# captivate_bswp.net
KiCad netlist of a schematic drawn in Altium Designer
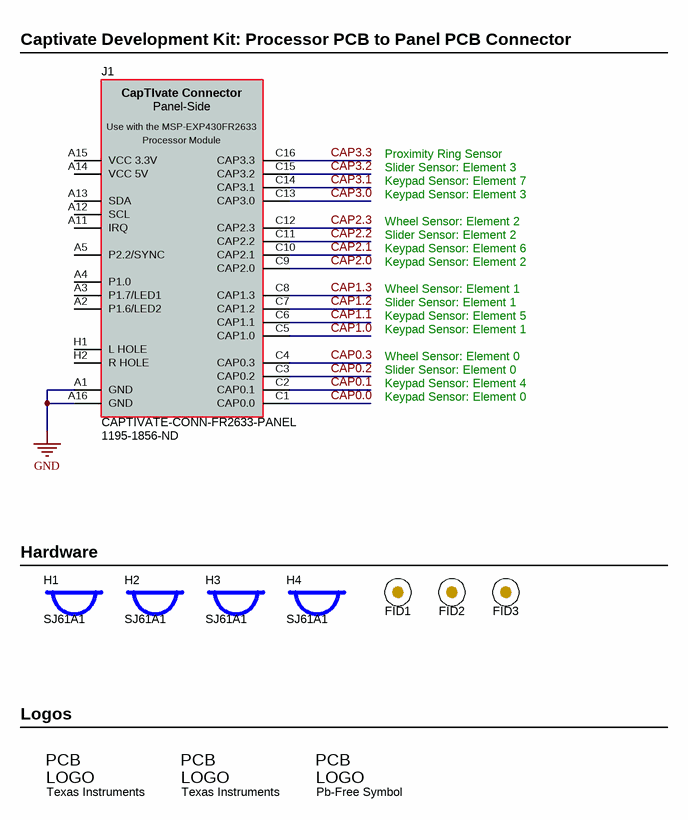
[diagram p0: captivate_bswp.SchDoc]

(export (version "E")
  (design (tool "Eeschema 10.0.6"))
  (components
    (comp (ref "FID1")
      (value "Fiducial")
      (footprint "Fiducial10-20")
      (description "Fiducial mark.  There is nothing to buy or mount.")
      (fields (field (name "SYMBOLCREATOR") "codlsc") (field (name "PUBLISHER") "Texas Instruments"))
      (libsource (lib "MiscParts") (part "Fiducial"))
    )
    (comp (ref "FID2")
      (value "Fiducial")
      (footprint "Fiducial10-20")
      (description "Fiducial mark.  There is nothing to buy or mount.")
      (fields (field (name "SYMBOLCREATOR") "codlsc") (field (name "PUBLISHER") "Texas Instruments"))
      (libsource (lib "MiscParts") (part "Fiducial"))
    )
    (comp (ref "FID3")
      (value "Fiducial")
      (footprint "Fiducial10-20")
      (description "Fiducial mark.  There is nothing to buy or mount.")
      (fields (field (name "SYMBOLCREATOR") "codlsc") (field (name "PUBLISHER") "Texas Instruments"))
      (libsource (lib "MiscParts") (part "Fiducial"))
    )
    (comp (ref "H1")
      (value "SJ61A1")
      (footprint "Bumpon_SJ61A1")
      (description "Bumpon, Cylindrical, 0.312 X 0.200, Black")
      (fields
        (field (name "MANUFACTURER") "3M")
        (field (name "SYMBOLCREATOR") "a0412235")
        (field (name "PUBLISHER") "Texas Instruments")
      )
      (libsource (lib "Hardware") (part "SJ61A1"))
    )
    (comp (ref "H2")
      (value "SJ61A1")
      (footprint "Bumpon_SJ61A1")
      (description "Bumpon, Cylindrical, 0.312 X 0.200, Black")
      (fields
        (field (name "MANUFACTURER") "3M")
        (field (name "SYMBOLCREATOR") "a0412235")
        (field (name "PUBLISHER") "Texas Instruments")
      )
      (libsource (lib "Hardware") (part "SJ61A1"))
    )
    (comp (ref "H3")
      (value "SJ61A1")
      (footprint "Bumpon_SJ61A1")
      (description "Bumpon, Cylindrical, 0.312 X 0.200, Black")
      (fields
        (field (name "MANUFACTURER") "3M")
        (field (name "SYMBOLCREATOR") "a0412235")
        (field (name "PUBLISHER") "Texas Instruments")
      )
      (libsource (lib "Hardware") (part "SJ61A1"))
    )
    (comp (ref "H4")
      (value "SJ61A1")
      (footprint "Bumpon_SJ61A1")
      (description "Bumpon, Cylindrical, 0.312 X 0.200, Black")
      (fields
        (field (name "MANUFACTURER") "3M")
        (field (name "SYMBOLCREATOR") "a0412235")
        (field (name "PUBLISHER") "Texas Instruments")
      )
      (libsource (lib "Hardware") (part "SJ61A1"))
    )
    (comp (ref "J1")
      (value "CAPTIVATE-CONN-FR2633-PANEL")
      (footprint "CAPTIVATE-CONN-48")
      (description "CapTIvate Panel-Side Connector, 3x16, 100mil, TH, RA, M, MSP-EXP430FR2633")
      (fields
        (field (name "MANUFACTURER") "Used in BOM report")
        (field (name "SUPPLIER PART NUMBER 1") "1195-1856-ND")
        (field (name "SYMBOLCREATOR") "a0273983")
      )
      (libsource (lib "CapTIvate_Connector") (part "CAPTIVATE-CONN-MSP-EXP430FR2633-PANEL"))
    )
    (comp (ref "LeadFreeLogo")
      (value "Pb-Free Symbol")
      (footprint "Pb-Free_Overlay_Medium")
      (fields (field (name "SYMBOLCREATOR") "a0412235") (field (name "PUBLISHER") "Texas Instruments"))
      (libsource (lib "Logos") (part "Pb-Free"))
    )
    (comp (ref "TI_LOGO_1")
      (value "Texas Instruments")
      (footprint "TI_Horizontal_Overlay_Medium")
      (description "Texas Instrument Corporate Signature")
      (fields (field (name "SYMBOLCREATOR") "a0412235") (field (name "PUBLISHER") "Texas Instruments"))
      (libsource (lib "Logos") (part "TI_Logo"))
    )
    (comp (ref "TI_LOGO_2")
      (value "Texas Instruments")
      (footprint "TI_Horizontal_Overlay_Medium")
      (description "Texas Instrument Corporate Signature")
      (fields (field (name "SYMBOLCREATOR") "a0412235") (field (name "PUBLISHER") "Texas Instruments"))
      (libsource (lib "Logos") (part "TI_Logo"))
    )
  )
  (nets
    (net (code "1") (name "/CAP0.0") (class "Default")
      (node (ref "J1") (pin "C1") (pinfunction "CAP0.0_C1") (pintype "passive"))
    )
    (net (code "2") (name "/CAP0.1") (class "Default")
      (node (ref "J1") (pin "C2") (pinfunction "CAP0.1_C2") (pintype "passive"))
    )
    (net (code "3") (name "/CAP0.2") (class "Default")
      (node (ref "J1") (pin "C3") (pinfunction "CAP0.2_C3") (pintype "passive"))
    )
    (net (code "4") (name "/CAP0.3") (class "Default")
      (node (ref "J1") (pin "C4") (pinfunction "CAP0.3_C4") (pintype "passive"))
    )
    (net (code "5") (name "/CAP1.0") (class "Default")
      (node (ref "J1") (pin "C5") (pinfunction "CAP1.0_C5") (pintype "passive"))
    )
    (net (code "6") (name "/CAP1.1") (class "Default")
      (node (ref "J1") (pin "C6") (pinfunction "CAP1.1_C6") (pintype "passive"))
    )
    (net (code "7") (name "/CAP1.2") (class "Default")
      (node (ref "J1") (pin "C7") (pinfunction "CAP1.2_C7") (pintype "passive"))
    )
    (net (code "8") (name "/CAP1.3") (class "Default")
      (node (ref "J1") (pin "C8") (pinfunction "CAP1.3_C8") (pintype "passive"))
    )
    (net (code "9") (name "/CAP2.0") (class "Default")
      (node (ref "J1") (pin "C9") (pinfunction "CAP2.0_C9") (pintype "passive"))
    )
    (net (code "10") (name "/CAP2.1") (class "Default")
      (node (ref "J1") (pin "C10") (pinfunction "CAP2.1_C10") (pintype "passive"))
    )
    (net (code "11") (name "/CAP2.2") (class "Default")
      (node (ref "J1") (pin "C11") (pinfunction "CAP2.2_C11") (pintype "passive"))
    )
    (net (code "12") (name "/CAP2.3") (class "Default")
      (node (ref "J1") (pin "C12") (pinfunction "CAP2.3_C12") (pintype "passive"))
    )
    (net (code "13") (name "/CAP3.0") (class "Default")
      (node (ref "J1") (pin "C13") (pinfunction "CAP3.0_C13") (pintype "passive"))
    )
    (net (code "14") (name "/CAP3.1") (class "Default")
      (node (ref "J1") (pin "C14") (pinfunction "CAP3.1_C14") (pintype "passive"))
    )
    (net (code "15") (name "/CAP3.2") (class "Default")
      (node (ref "J1") (pin "C15") (pinfunction "CAP3.2_C15") (pintype "passive"))
    )
    (net (code "16") (name "/CAP3.3") (class "Default")
      (node (ref "J1") (pin "C16") (pinfunction "CAP3.3_C16") (pintype "passive"))
    )
    (net (code "17") (name "GND") (class "Default")
      (node (ref "J1") (pin "A1") (pinfunction "GND_A1") (pintype "power_in"))
      (node (ref "J1") (pin "A16") (pinfunction "GND_A16") (pintype "power_in"))
    )
    (net (code "18") (name "unconnected-(J1-IRQ-PadA11)") (class "Default")
      (node (ref "J1") (pin "A11") (pinfunction "IRQ_A11") (pintype "open_collector"))
    )
    (net (code "19") (name "unconnected-(J1-L_HOLE-PadH1)") (class "Default")
      (node (ref "J1") (pin "H1") (pinfunction "L_HOLE_H1") (pintype "passive"))
    )
    (net (code "20") (name "unconnected-(J1-P1.0-PadA4)") (class "Default")
      (node (ref "J1") (pin "A4") (pinfunction "P1.0_A4") (pintype "open_collector"))
    )
    (net (code "21") (name "unconnected-(J1-P1.6{slash}LED2-PadA2)") (class "Default")
      (node (ref "J1") (pin "A2") (pinfunction "P1.6/LED2_A2") (pintype "open_collector"))
    )
    (net (code "22") (name "unconnected-(J1-P1.7{slash}LED1-PadA3)") (class "Default")
      (node (ref "J1") (pin "A3") (pinfunction "P1.7/LED1_A3") (pintype "open_collector"))
    )
    (net (code "23") (name "unconnected-(J1-P2.2{slash}SYNC-PadA5)") (class "Default")
      (node (ref "J1") (pin "A5") (pinfunction "P2.2/SYNC_A5") (pintype "open_collector"))
    )
    (net (code "24") (name "unconnected-(J1-R_HOLE-PadH2)") (class "Default")
      (node (ref "J1") (pin "H2") (pinfunction "R_HOLE_H2") (pintype "passive"))
    )
    (net (code "25") (name "unconnected-(J1-SCL-PadA12)") (class "Default")
      (node (ref "J1") (pin "A12") (pinfunction "SCL_A12") (pintype "open_collector"))
    )
    (net (code "26") (name "unconnected-(J1-SDA-PadA13)") (class "Default")
      (node (ref "J1") (pin "A13") (pinfunction "SDA_A13") (pintype "open_collector"))
    )
    (net (code "27") (name "unconnected-(J1-VCC_3.3V-PadA15)") (class "Default")
      (node (ref "J1") (pin "A15") (pinfunction "VCC_3.3V_A15") (pintype "power_in"))
    )
    (net (code "28") (name "unconnected-(J1-VCC_5V-PadA14)") (class "Default")
      (node (ref "J1") (pin "A14") (pinfunction "VCC_5V_A14") (pintype "power_in"))
    )
  )
)
